# Grove_-_IMU_10DOF_v1_0.net
KiCad netlist of a schematic drawn in EAGLE
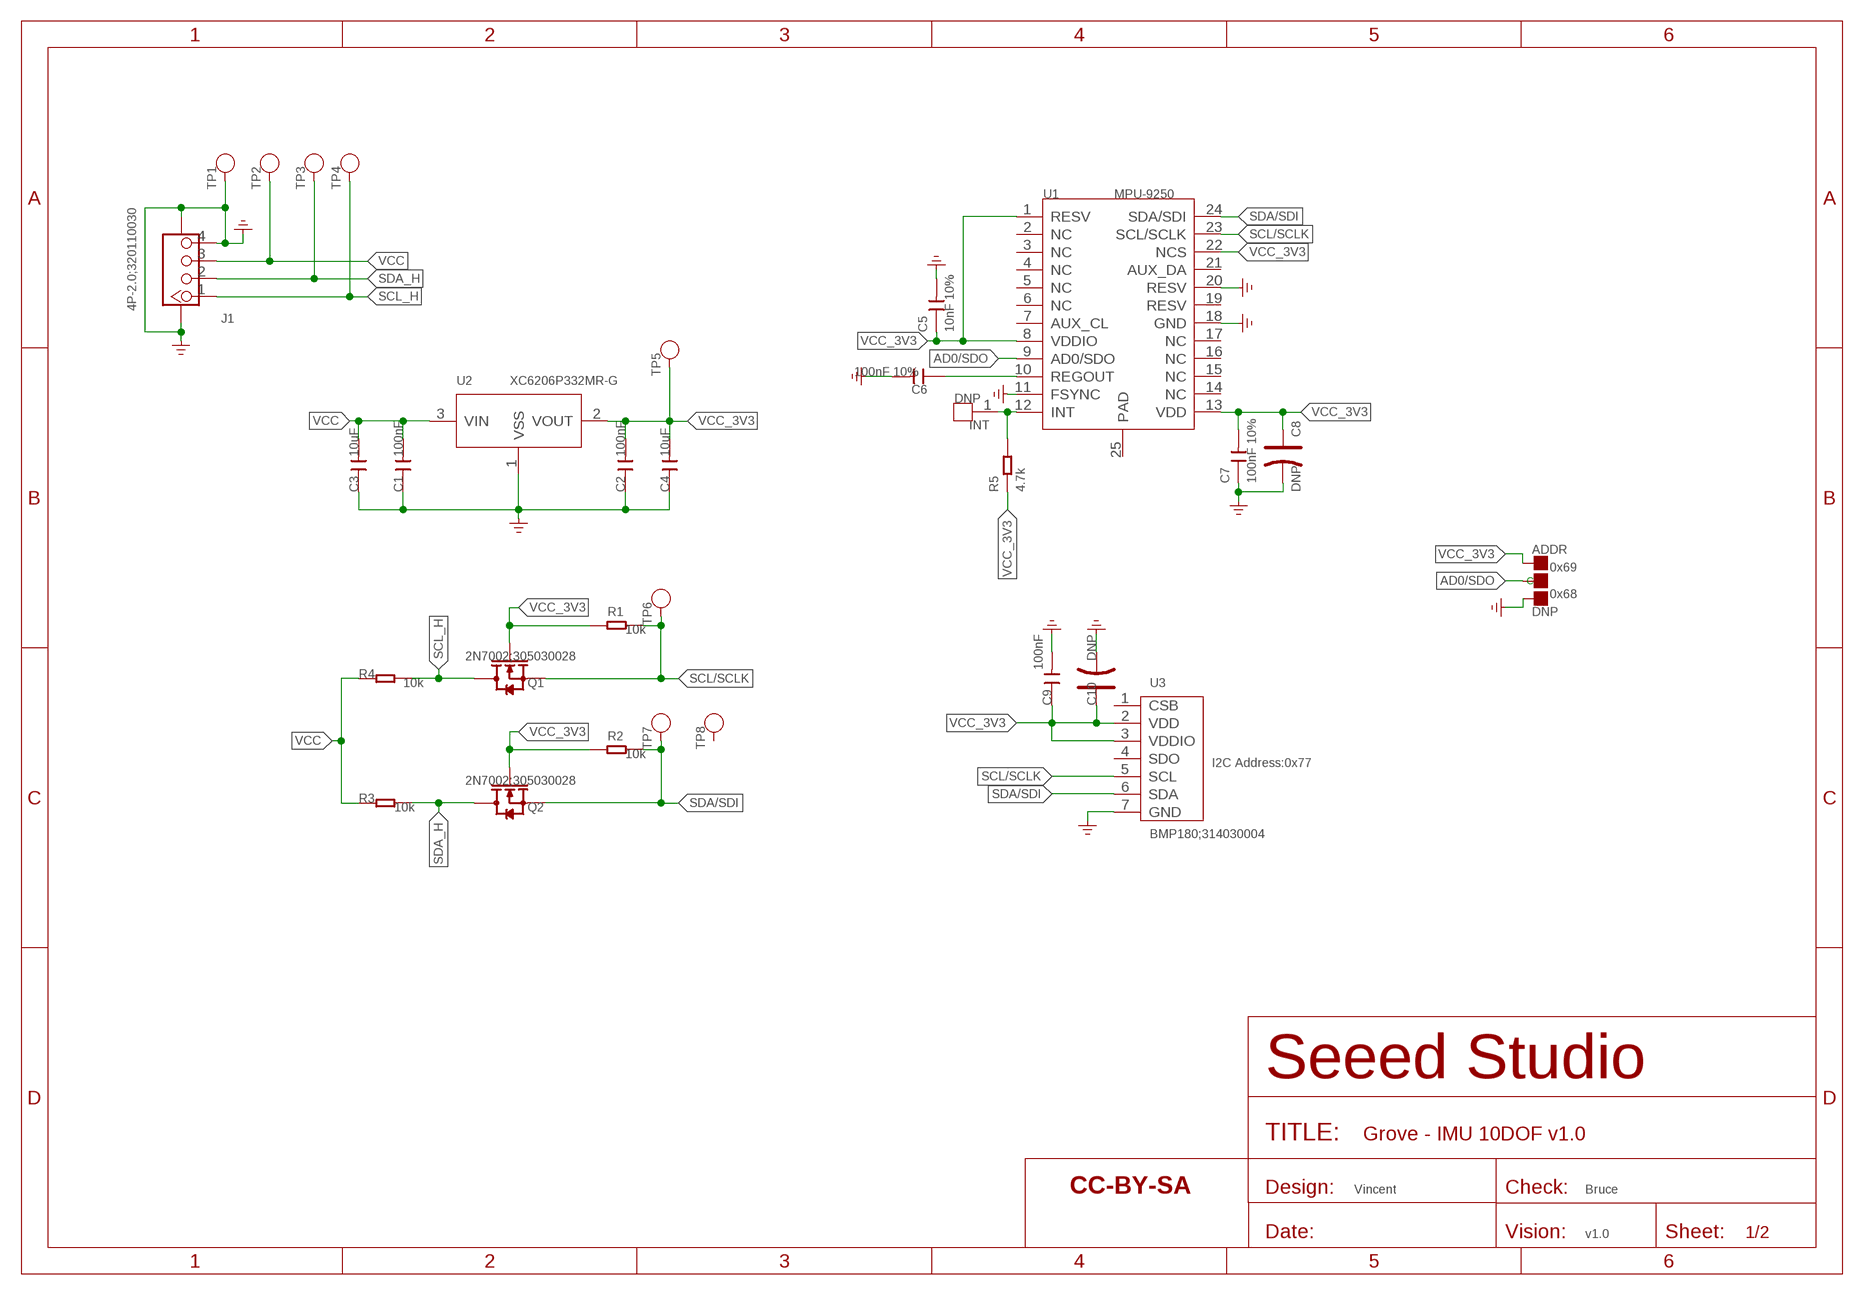
[diagram p0: schematic, sheet 1]

(export (version "E")
  (design (tool "Eeschema 10.0.6"))
  (components
    (comp (ref "ADDR")
      (value "DNP")
      (footprint "eagle-import:3P-SMD-L4.1_W1.5MM")
      (libsource (lib "eagle-import") (part "PAD-JUMPER-3P-4040"))
    )
    (comp (ref "C1")
      (value "100nF")
      (footprint "eagle-import:C0603")
      (libsource (lib "eagle-import") (part "CAP-0603"))
    )
    (comp (ref "C2")
      (value "100nF")
      (footprint "eagle-import:C0603")
      (libsource (lib "eagle-import") (part "CAP-0603"))
    )
    (comp (ref "C3")
      (value "10uF")
      (footprint "eagle-import:C0805")
      (libsource (lib "eagle-import") (part "CAP-0805"))
    )
    (comp (ref "C4")
      (value "10uF")
      (footprint "eagle-import:C0805")
      (libsource (lib "eagle-import") (part "CAP-0805"))
    )
    (comp (ref "C5")
      (value "10nF 10%")
      (footprint "eagle-import:C0603")
      (libsource (lib "eagle-import") (part "CAP-0603"))
    )
    (comp (ref "C6")
      (value "100nF 10%")
      (footprint "eagle-import:C0603")
      (libsource (lib "eagle-import") (part "CAP-0603"))
    )
    (comp (ref "C7")
      (value "100nF 10%")
      (footprint "eagle-import:C0603")
      (libsource (lib "eagle-import") (part "CAP-0603"))
    )
    (comp (ref "C8")
      (value "DNP")
      (footprint "eagle-import:AVX-A")
      (libsource (lib "eagle-import") (part "CAP-POLAR-AVX-A"))
    )
    (comp (ref "C9")
      (value "100nF")
      (footprint "eagle-import:C0603")
      (libsource (lib "eagle-import") (part "CAP-0603"))
    )
    (comp (ref "C10")
      (value "DNP")
      (footprint "eagle-import:AVX-A")
      (libsource (lib "eagle-import") (part "CAP-POLAR-AVX-A"))
    )
    (comp (ref "INT")
      (value "DNP")
      (footprint "eagle-import:1P-65_35MIL")
      (libsource (lib "eagle-import") (part "HEADER-1P-35"))
    )
    (comp (ref "J1")
      (value "4P-2.0;320110030")
      (footprint "eagle-import:4P-SMD-2.0")
      (libsource (lib "eagle-import") (part "GROVE-CONNECTOR-SMD'DD'"))
    )
    (comp (ref "Q1")
      (value "2N7002;305030028")
      (footprint "eagle-import:SOT-23")
      (libsource (lib "eagle-import") (part "MOSFET-N'SOT23'"))
    )
    (comp (ref "Q2")
      (value "2N7002;305030028")
      (footprint "eagle-import:SOT-23")
      (libsource (lib "eagle-import") (part "MOSFET-N'SOT23'"))
    )
    (comp (ref "R1")
      (value "10k")
      (footprint "eagle-import:R0603")
      (libsource (lib "eagle-import") (part "RES-0603"))
    )
    (comp (ref "R2")
      (value "10k")
      (footprint "eagle-import:R0603")
      (libsource (lib "eagle-import") (part "RES-0603"))
    )
    (comp (ref "R3")
      (value "10k")
      (footprint "eagle-import:R0603")
      (libsource (lib "eagle-import") (part "RES-0603"))
    )
    (comp (ref "R4")
      (value "10k")
      (footprint "eagle-import:R0603")
      (libsource (lib "eagle-import") (part "RES-0603"))
    )
    (comp (ref "R5")
      (value "4.7k")
      (footprint "eagle-import:R0603")
      (libsource (lib "eagle-import") (part "RES-0603"))
    )
    (comp (ref "TP1")
      (value "DNP")
      (footprint "eagle-import:TP-D45MIL")
      (libsource (lib "eagle-import") (part "PAD-TEST-POINT'4545'"))
    )
    (comp (ref "TP2")
      (value "DNP")
      (footprint "eagle-import:TP-D45MIL")
      (libsource (lib "eagle-import") (part "PAD-TEST-POINT'4545'"))
    )
    (comp (ref "TP3")
      (value "DNP")
      (footprint "eagle-import:TP-D45MIL")
      (libsource (lib "eagle-import") (part "PAD-TEST-POINT'4545'"))
    )
    (comp (ref "TP4")
      (value "DNP")
      (footprint "eagle-import:TP-D45MIL")
      (libsource (lib "eagle-import") (part "PAD-TEST-POINT'4545'"))
    )
    (comp (ref "TP5")
      (value "DNP")
      (footprint "eagle-import:TP-D45MIL")
      (libsource (lib "eagle-import") (part "PAD-TEST-POINT'4545'"))
    )
    (comp (ref "TP6")
      (value "DNP")
      (footprint "eagle-import:TP-D45MIL")
      (libsource (lib "eagle-import") (part "PAD-TEST-POINT'4545'"))
    )
    (comp (ref "TP7")
      (value "DNP")
      (footprint "eagle-import:TP-D45MIL")
      (libsource (lib "eagle-import") (part "PAD-TEST-POINT'4545'"))
    )
    (comp (ref "TP8")
      (value "DNP")
      (footprint "eagle-import:TP-D45MIL")
      (libsource (lib "eagle-import") (part "PAD-TEST-POINT'4545'"))
    )
    (comp (ref "U$1")
      (value "SEEEDSTUDIO-OPEN-SCH-FRAME")
      (footprint "eagle-import:SEEEDSTUDIO-PCB-FRAME")
      (libsource (lib "eagle-import") (part "SEEEDSTUDIO-OPEN-SCH-FRAME"))
    )
    (comp (ref "U1")
      (value "MPU-9250")
      (footprint "eagle-import:LEAD-QFN24")
      (libsource (lib "eagle-import") (part "MPU-9250"))
    )
    (comp (ref "U2")
      (value "XC6206P332MR-G")
      (footprint "eagle-import:SOT-23")
      (libsource (lib "eagle-import") (part "PMIC-XC6206PMR"))
    )
    (comp (ref "U3")
      (value "BMP180;314030004")
      (footprint "eagle-import:LGA-7")
      (libsource (lib "eagle-import") (part "BMP180"))
    )
  )
  (nets
    (net (code "1") (name "AD0{slash}SDO") (class "Default")
      (node (ref "ADDR") (pin "MM") (pinfunction "C_MM") (pintype "bidirectional"))
      (node (ref "U1") (pin "9") (pinfunction "AD0/SDO_9") (pintype "bidirectional"))
    )
    (net (code "2") (name "GND") (class "Default")
      (node (ref "ADDR") (pin "11") (pinfunction "R_11") (pintype "bidirectional"))
      (node (ref "C1") (pin "1") (pinfunction "1_1") (pintype "passive"))
      (node (ref "C10") (pin "-") (pinfunction "-_-") (pintype "passive"))
      (node (ref "C2") (pin "1") (pinfunction "1_1") (pintype "passive"))
      (node (ref "C3") (pin "1") (pinfunction "1_1") (pintype "passive"))
      (node (ref "C4") (pin "1") (pinfunction "1_1") (pintype "passive"))
      (node (ref "C5") (pin "2") (pinfunction "2_2") (pintype "passive"))
      (node (ref "C6") (pin "2") (pinfunction "2_2") (pintype "passive"))
      (node (ref "C7") (pin "1") (pinfunction "1_1") (pintype "passive"))
      (node (ref "C8") (pin "-") (pinfunction "-_-") (pintype "passive"))
      (node (ref "C9") (pin "2") (pinfunction "2_2") (pintype "passive"))
      (node (ref "J1") (pin "4") (pinfunction "4_4") (pintype "bidirectional"))
      (node (ref "J1") (pin "SS1") (pinfunction "SS1_SS1") (pintype "bidirectional"))
      (node (ref "J1") (pin "SS2") (pinfunction "SS2_SS2") (pintype "bidirectional"))
      (node (ref "TP1") (pin "T") (pinfunction "T_T") (pintype "bidirectional"))
      (node (ref "U1") (pin "11") (pinfunction "FSYNC_11") (pintype "bidirectional"))
      (node (ref "U1") (pin "18") (pinfunction "GND_18") (pintype "bidirectional"))
      (node (ref "U1") (pin "20") (pinfunction "RESV_20") (pintype "bidirectional"))
      (node (ref "U2") (pin "1") (pinfunction "VSS_1") (pintype "power_in"))
      (node (ref "U3") (pin "7") (pinfunction "GND_7") (pintype "bidirectional"))
    )
    (net (code "3") (name "Net-(U1-INT)") (class "Default")
      (node (ref "INT") (pin "1") (pinfunction "1_1") (pintype "bidirectional"))
      (node (ref "R5") (pin "2") (pinfunction "2_2") (pintype "passive"))
      (node (ref "U1") (pin "12") (pinfunction "INT_12") (pintype "bidirectional"))
    )
    (net (code "4") (name "Net-(U1-REGOUT)") (class "Default")
      (node (ref "C6") (pin "1") (pinfunction "1_1") (pintype "passive"))
      (node (ref "U1") (pin "10") (pinfunction "REGOUT_10") (pintype "bidirectional"))
    )
    (net (code "5") (name "SCL_H") (class "Default")
      (node (ref "J1") (pin "1") (pinfunction "1_1") (pintype "bidirectional"))
      (node (ref "Q1") (pin "3") (pinfunction "D_3") (pintype "passive"))
      (node (ref "R4") (pin "2") (pinfunction "2_2") (pintype "passive"))
      (node (ref "TP4") (pin "T") (pinfunction "T_T") (pintype "bidirectional"))
    )
    (net (code "6") (name "SCL{slash}SCLK") (class "Default")
      (node (ref "Q1") (pin "2") (pinfunction "S_2") (pintype "passive"))
      (node (ref "R1") (pin "2") (pinfunction "2_2") (pintype "passive"))
      (node (ref "TP6") (pin "T") (pinfunction "T_T") (pintype "bidirectional"))
      (node (ref "U1") (pin "23") (pinfunction "SCL/SCLK_23") (pintype "bidirectional"))
      (node (ref "U3") (pin "5") (pinfunction "SCL_5") (pintype "bidirectional"))
    )
    (net (code "7") (name "SDA_H") (class "Default")
      (node (ref "J1") (pin "2") (pinfunction "2_2") (pintype "bidirectional"))
      (node (ref "Q2") (pin "3") (pinfunction "D_3") (pintype "passive"))
      (node (ref "R3") (pin "2") (pinfunction "2_2") (pintype "passive"))
      (node (ref "TP3") (pin "T") (pinfunction "T_T") (pintype "bidirectional"))
    )
    (net (code "8") (name "SDA{slash}SDI") (class "Default")
      (node (ref "Q2") (pin "2") (pinfunction "S_2") (pintype "passive"))
      (node (ref "R2") (pin "2") (pinfunction "2_2") (pintype "passive"))
      (node (ref "TP7") (pin "T") (pinfunction "T_T") (pintype "bidirectional"))
      (node (ref "U1") (pin "24") (pinfunction "SDA/SDI_24") (pintype "bidirectional"))
      (node (ref "U3") (pin "6") (pinfunction "SDA_6") (pintype "bidirectional"))
    )
    (net (code "9") (name "VCC") (class "Default")
      (node (ref "C1") (pin "2") (pinfunction "2_2") (pintype "passive"))
      (node (ref "C3") (pin "2") (pinfunction "2_2") (pintype "passive"))
      (node (ref "J1") (pin "3") (pinfunction "3_3") (pintype "bidirectional"))
      (node (ref "R3") (pin "1") (pinfunction "1_1") (pintype "passive"))
      (node (ref "R4") (pin "1") (pinfunction "1_1") (pintype "passive"))
      (node (ref "TP2") (pin "T") (pinfunction "T_T") (pintype "bidirectional"))
      (node (ref "U2") (pin "3") (pinfunction "VIN_3") (pintype "input"))
    )
    (net (code "10") (name "VCC_3V3") (class "Default")
      (node (ref "ADDR") (pin "00") (pinfunction "L_00") (pintype "bidirectional"))
      (node (ref "C10") (pin "+") (pinfunction "+_+") (pintype "passive"))
      (node (ref "C2") (pin "2") (pinfunction "2_2") (pintype "passive"))
      (node (ref "C4") (pin "2") (pinfunction "2_2") (pintype "passive"))
      (node (ref "C5") (pin "1") (pinfunction "1_1") (pintype "passive"))
      (node (ref "C7") (pin "2") (pinfunction "2_2") (pintype "passive"))
      (node (ref "C8") (pin "+") (pinfunction "+_+") (pintype "passive"))
      (node (ref "C9") (pin "1") (pinfunction "1_1") (pintype "passive"))
      (node (ref "Q1") (pin "1") (pinfunction "G_1") (pintype "passive"))
      (node (ref "Q2") (pin "1") (pinfunction "G_1") (pintype "passive"))
      (node (ref "R1") (pin "1") (pinfunction "1_1") (pintype "passive"))
      (node (ref "R2") (pin "1") (pinfunction "1_1") (pintype "passive"))
      (node (ref "R5") (pin "1") (pinfunction "1_1") (pintype "passive"))
      (node (ref "TP5") (pin "T") (pinfunction "T_T") (pintype "bidirectional"))
      (node (ref "U1") (pin "1") (pinfunction "RESV_1") (pintype "bidirectional"))
      (node (ref "U1") (pin "13") (pinfunction "VDD_13") (pintype "bidirectional"))
      (node (ref "U1") (pin "22") (pinfunction "NCS_22") (pintype "bidirectional"))
      (node (ref "U1") (pin "8") (pinfunction "VDDIO_8") (pintype "bidirectional"))
      (node (ref "U2") (pin "2") (pinfunction "VOUT_2") (pintype "output"))
      (node (ref "U3") (pin "2") (pinfunction "VDD_2") (pintype "bidirectional"))
      (node (ref "U3") (pin "3") (pinfunction "VDDIO_3") (pintype "bidirectional"))
    )
    (net (code "11") (name "unconnected-(TP8-PadT)") (class "Default")
      (node (ref "TP8") (pin "T") (pinfunction "T_T") (pintype "bidirectional"))
    )
    (net (code "12") (name "unconnected-(U1-AUX_CL-Pad7)") (class "Default")
      (node (ref "U1") (pin "7") (pinfunction "AUX_CL_7") (pintype "bidirectional"))
    )
    (net (code "13") (name "unconnected-(U1-AUX_DA-Pad21)") (class "Default")
      (node (ref "U1") (pin "21") (pinfunction "AUX_DA_21") (pintype "bidirectional"))
    )
    (net (code "14") (name "unconnected-(U1-NC-Pad2)") (class "Default")
      (node (ref "U1") (pin "2") (pinfunction "NC_2") (pintype "bidirectional"))
    )
    (net (code "15") (name "unconnected-(U1-NC-Pad3)") (class "Default")
      (node (ref "U1") (pin "3") (pinfunction "NC_3") (pintype "bidirectional"))
    )
    (net (code "16") (name "unconnected-(U1-NC-Pad4)") (class "Default")
      (node (ref "U1") (pin "4") (pinfunction "NC_4") (pintype "bidirectional"))
    )
    (net (code "17") (name "unconnected-(U1-NC-Pad5)") (class "Default")
      (node (ref "U1") (pin "5") (pinfunction "NC_5") (pintype "bidirectional"))
    )
    (net (code "18") (name "unconnected-(U1-NC-Pad6)") (class "Default")
      (node (ref "U1") (pin "6") (pinfunction "NC_6") (pintype "bidirectional"))
    )
    (net (code "19") (name "unconnected-(U1-NC-Pad14)") (class "Default")
      (node (ref "U1") (pin "14") (pinfunction "NC_14") (pintype "bidirectional"))
    )
    (net (code "20") (name "unconnected-(U1-NC-Pad15)") (class "Default")
      (node (ref "U1") (pin "15") (pinfunction "NC_15") (pintype "bidirectional"))
    )
    (net (code "21") (name "unconnected-(U1-NC-Pad16)") (class "Default")
      (node (ref "U1") (pin "16") (pinfunction "NC_16") (pintype "bidirectional"))
    )
    (net (code "22") (name "unconnected-(U1-NC-Pad17)") (class "Default")
      (node (ref "U1") (pin "17") (pinfunction "NC_17") (pintype "bidirectional"))
    )
    (net (code "23") (name "unconnected-(U1-PAD-Pad25)") (class "Default")
      (node (ref "U1") (pin "25") (pinfunction "PAD_25") (pintype "bidirectional"))
    )
    (net (code "24") (name "unconnected-(U1-RESV-Pad19)") (class "Default")
      (node (ref "U1") (pin "19") (pinfunction "RESV_19") (pintype "bidirectional"))
    )
    (net (code "25") (name "unconnected-(U3-CSB-Pad1)") (class "Default")
      (node (ref "U3") (pin "1") (pinfunction "CSB_1") (pintype "bidirectional"))
    )
    (net (code "26") (name "unconnected-(U3-SDO-Pad4)") (class "Default")
      (node (ref "U3") (pin "4") (pinfunction "SDO_4") (pintype "bidirectional"))
    )
  )
)
